# S03_Power_Management.net
KiCad netlist of a schematic drawn in Altium Designer
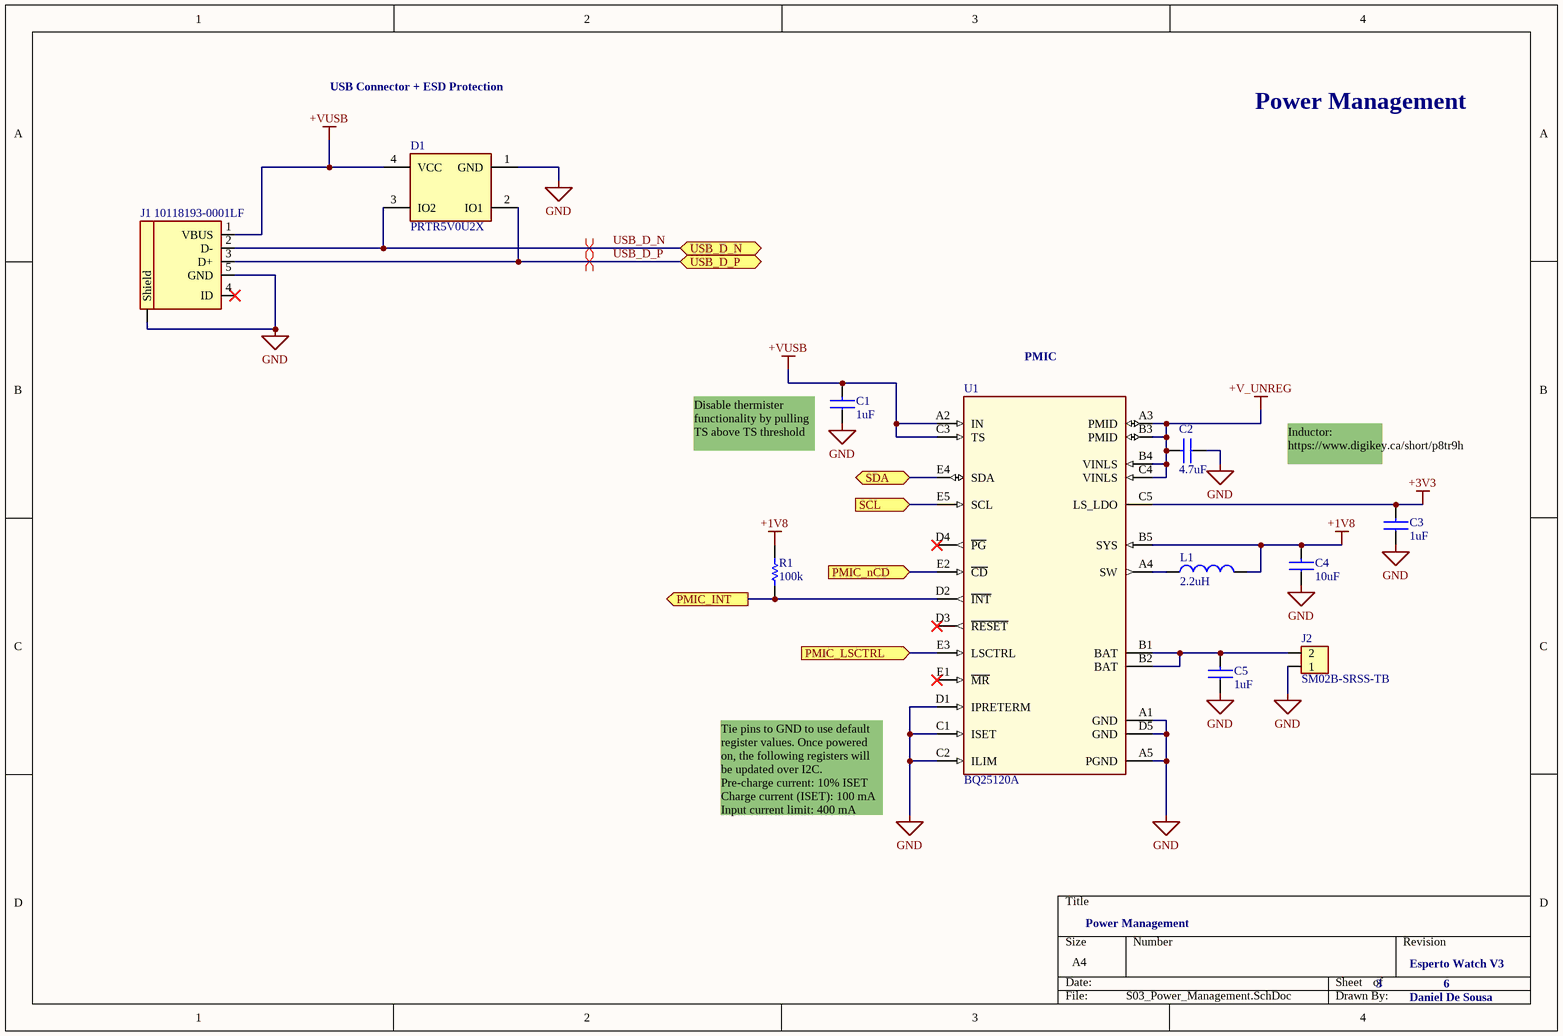
[diagram p0: S03_Power_Management.SchDoc]

(export (version "E")
  (design (tool "Eeschema 10.0.6"))
  (components
    (comp (ref "C1")
      (value "1uF")
      (footprint "CC_1005_0402_N")
      (description "Capacitor")
      (libsource (lib "Esperto") (part "Capacitor"))
    )
    (comp (ref "C2")
      (value "4.7uF")
      (footprint "CC_1005_0402_N")
      (description "Capacitor")
      (libsource (lib "Esperto") (part "Capacitor"))
    )
    (comp (ref "C3")
      (value "1uF")
      (footprint "CC_1005_0402_N")
      (description "Capacitor")
      (libsource (lib "Esperto") (part "Capacitor"))
    )
    (comp (ref "C4")
      (value "10uF")
      (footprint "CC_1005_0402_N")
      (description "Capacitor")
      (libsource (lib "Esperto") (part "Capacitor"))
    )
    (comp (ref "C5")
      (value "1uF")
      (footprint "CC_1005_0402_N")
      (description "Capacitor")
      (libsource (lib "Esperto") (part "Capacitor"))
    )
    (comp (ref "D1")
      (value "PRTR5V0U2X")
      (footprint "PRTR5V0U2X")
      (description "Ultra low capacitance double rail-to-rail ESD protection diode")
      (fields
        (field (name "MANUFACTURER") "NXP")
        (field (name "2ND SOURCE PART NUMBER") "152-4157")
        (field (name "PUBLISHER") "Nordic Semiconductor")
      )
      (libsource (lib "Esperto") (part "PRTR5V0U2X"))
    )
    (comp (ref "J1")
      (value "10118193-0001LF")
      (footprint "CONN_USB_MICRO_B")
      (description "MicroUSB-B-SMT")
      (fields
        (field (name "PART NUMBER") "USB-Micro-B-RA-SMD-PiP")
        (field (name "MANUFACTURER") "Allen Creations Corp.")
        (field (name "PUBLISHER") "Nordic Semiconductor")
      )
      (libsource (lib "Esperto") (part "CONN_USB"))
    )
    (comp (ref "J2")
      (value "SM02B-SRSS-TB")
      (footprint "SM02B-SRSS-TB")
      (description "1.0mm pitch connector side entry SMD")
      (fields
        (field (name "MANUFACTURER") "JST")
        (field (name "MANUFACTURER PART NUMBER") "SM02B-SRSS-TB(LF)(SN)")
        (field (name "PUBLISHER") "Nordic Semiconductor")
      )
      (libsource (lib "Esperto") (part "SM02B-SRSS-TB"))
    )
    (comp (ref "L1")
      (value "2.2uH")
      (footprint "IND_1608_0603_N")
      (description "Inductor")
      (libsource (lib "Esperto") (part "Inductor_0603"))
    )
    (comp (ref "R1")
      (value "100k")
      (footprint "RC_1005_0402_N")
      (description "Resistor")
      (libsource (lib "Esperto") (part "Resistor"))
    )
    (comp (ref "U1")
      (value "BQ25120A")
      (footprint "BQ25120A")
      (description "Battery Charge Management Solution")
      (fields
        (field (name "MANUFACTURER_PART_NUMBER") "BQ25120YFPR")
        (field (name "ALTERNATE_PARTNUMBER") "BQ25120YFPT")
        (field (name "COPYRIGHT") "Copyright (C) 2018 Accelerated Designs. All rights reserved")
      )
      (libsource (lib "Esperto") (part "BQ25120A"))
    )
  )
  (nets
    (net (code "1") (name "+1V8") (class "Default")
      (node (ref "C4") (pin "2") (pinfunction "2_2") (pintype "passive"))
      (node (ref "L1") (pin "2") (pinfunction "2_2") (pintype "passive"))
      (node (ref "R1") (pin "2") (pinfunction "2_2") (pintype "passive"))
      (node (ref "U1") (pin "B5") (pinfunction "SYS_B5") (pintype "input"))
    )
    (net (code "2") (name "+3V3") (class "Default")
      (node (ref "C3") (pin "2") (pinfunction "2_2") (pintype "passive"))
      (node (ref "U1") (pin "C5") (pinfunction "LS_LDO_C5") (pintype "power_in"))
    )
    (net (code "3") (name "+VUSB") (class "Default")
      (node (ref "C1") (pin "2") (pinfunction "2_2") (pintype "passive"))
      (node (ref "D1") (pin "4") (pinfunction "VCC_4") (pintype "passive"))
      (node (ref "J1") (pin "1") (pinfunction "VBUS_1") (pintype "power_in"))
      (node (ref "U1") (pin "A2") (pinfunction "IN_A2") (pintype "input"))
      (node (ref "U1") (pin "C3") (pinfunction "TS_C3") (pintype "input"))
    )
    (net (code "4") (name "+V_UNREG") (class "Default")
      (node (ref "C2") (pin "2") (pinfunction "2_2") (pintype "passive"))
      (node (ref "U1") (pin "A3") (pinfunction "PMID_A3") (pintype "bidirectional"))
      (node (ref "U1") (pin "B3") (pinfunction "PMID_B3") (pintype "bidirectional"))
      (node (ref "U1") (pin "B4") (pinfunction "VINLS_B4") (pintype "input"))
      (node (ref "U1") (pin "C4") (pinfunction "VINLS_C4") (pintype "input"))
    )
    (net (code "5") (name "/PMIC_INT") (class "Default")
      (node (ref "R1") (pin "1") (pinfunction "1_1") (pintype "passive"))
      (node (ref "U1") (pin "D2") (pinfunction "~{INT}_D2") (pintype "output"))
    )
    (net (code "6") (name "/PMIC_LSCTRL") (class "Default")
      (node (ref "U1") (pin "E3") (pinfunction "LSCTRL_E3") (pintype "input"))
    )
    (net (code "7") (name "/PMIC_nCD") (class "Default")
      (node (ref "U1") (pin "E2") (pinfunction "~{CD}_E2") (pintype "input"))
    )
    (net (code "8") (name "/SCL") (class "Default")
      (node (ref "U1") (pin "E5") (pinfunction "SCL_E5") (pintype "input"))
    )
    (net (code "9") (name "/SDA") (class "Default")
      (node (ref "U1") (pin "E4") (pinfunction "SDA_E4") (pintype "bidirectional"))
    )
    (net (code "10") (name "/USB_D_N") (class "Default")
      (node (ref "D1") (pin "3") (pinfunction "IO2_3") (pintype "passive"))
      (node (ref "J1") (pin "2") (pinfunction "D-_2") (pintype "passive"))
    )
    (net (code "11") (name "/USB_D_P") (class "Default")
      (node (ref "D1") (pin "2") (pinfunction "IO1_2") (pintype "passive"))
      (node (ref "J1") (pin "3") (pinfunction "D+_3") (pintype "passive"))
    )
    (net (code "12") (name "GND") (class "Default")
      (node (ref "C1") (pin "1") (pinfunction "1_1") (pintype "passive"))
      (node (ref "C2") (pin "1") (pinfunction "1_1") (pintype "passive"))
      (node (ref "C3") (pin "1") (pinfunction "1_1") (pintype "passive"))
      (node (ref "C4") (pin "1") (pinfunction "1_1") (pintype "passive"))
      (node (ref "C5") (pin "1") (pinfunction "1_1") (pintype "passive"))
      (node (ref "D1") (pin "1") (pinfunction "GND_1") (pintype "passive"))
      (node (ref "J1") (pin "5") (pinfunction "GND_5") (pintype "power_in"))
      (node (ref "J1") (pin "6") (pinfunction "Shield_6") (pintype "power_in"))
      (node (ref "J2") (pin "1") (pinfunction "1_1") (pintype "passive"))
      (node (ref "U1") (pin "A1") (pinfunction "GND_A1") (pintype "power_in"))
      (node (ref "U1") (pin "A5") (pinfunction "PGND_A5") (pintype "power_in"))
      (node (ref "U1") (pin "C1") (pinfunction "ISET_C1") (pintype "input"))
      (node (ref "U1") (pin "C2") (pinfunction "ILIM_C2") (pintype "input"))
      (node (ref "U1") (pin "D1") (pinfunction "IPRETERM_D1") (pintype "input"))
      (node (ref "U1") (pin "D5") (pinfunction "GND_D5") (pintype "power_in"))
    )
    (net (code "13") (name "Net-(C5-Pad2)") (class "Default")
      (node (ref "C5") (pin "2") (pinfunction "2_2") (pintype "passive"))
      (node (ref "J2") (pin "2") (pinfunction "2_2") (pintype "passive"))
      (node (ref "U1") (pin "B1") (pinfunction "BAT_B1") (pintype "power_in"))
      (node (ref "U1") (pin "B2") (pinfunction "BAT_B2") (pintype "power_in"))
    )
    (net (code "14") (name "Net-(U1-SW)") (class "Default")
      (node (ref "L1") (pin "1") (pinfunction "1_1") (pintype "passive"))
      (node (ref "U1") (pin "A4") (pinfunction "SW_A4") (pintype "output"))
    )
    (net (code "15") (name "unconnected-(J1-ID-Pad4)") (class "Default")
      (node (ref "J1") (pin "4") (pinfunction "ID_4") (pintype "passive+no_connect"))
    )
    (net (code "16") (name "unconnected-(U1-~{MR}-PadE1)") (class "Default")
      (node (ref "U1") (pin "E1") (pinfunction "~{MR}_E1") (pintype "input+no_connect"))
    )
    (net (code "17") (name "unconnected-(U1-~{PG}-PadD4)") (class "Default")
      (node (ref "U1") (pin "D4") (pinfunction "~{PG}_D4") (pintype "output+no_connect"))
    )
    (net (code "18") (name "unconnected-(U1-~{RESET}-PadD3)") (class "Default")
      (node (ref "U1") (pin "D3") (pinfunction "~{RESET}_D3") (pintype "output+no_connect"))
    )
  )
)
